# main.net
KiCad netlist of a schematic drawn in EAGLE
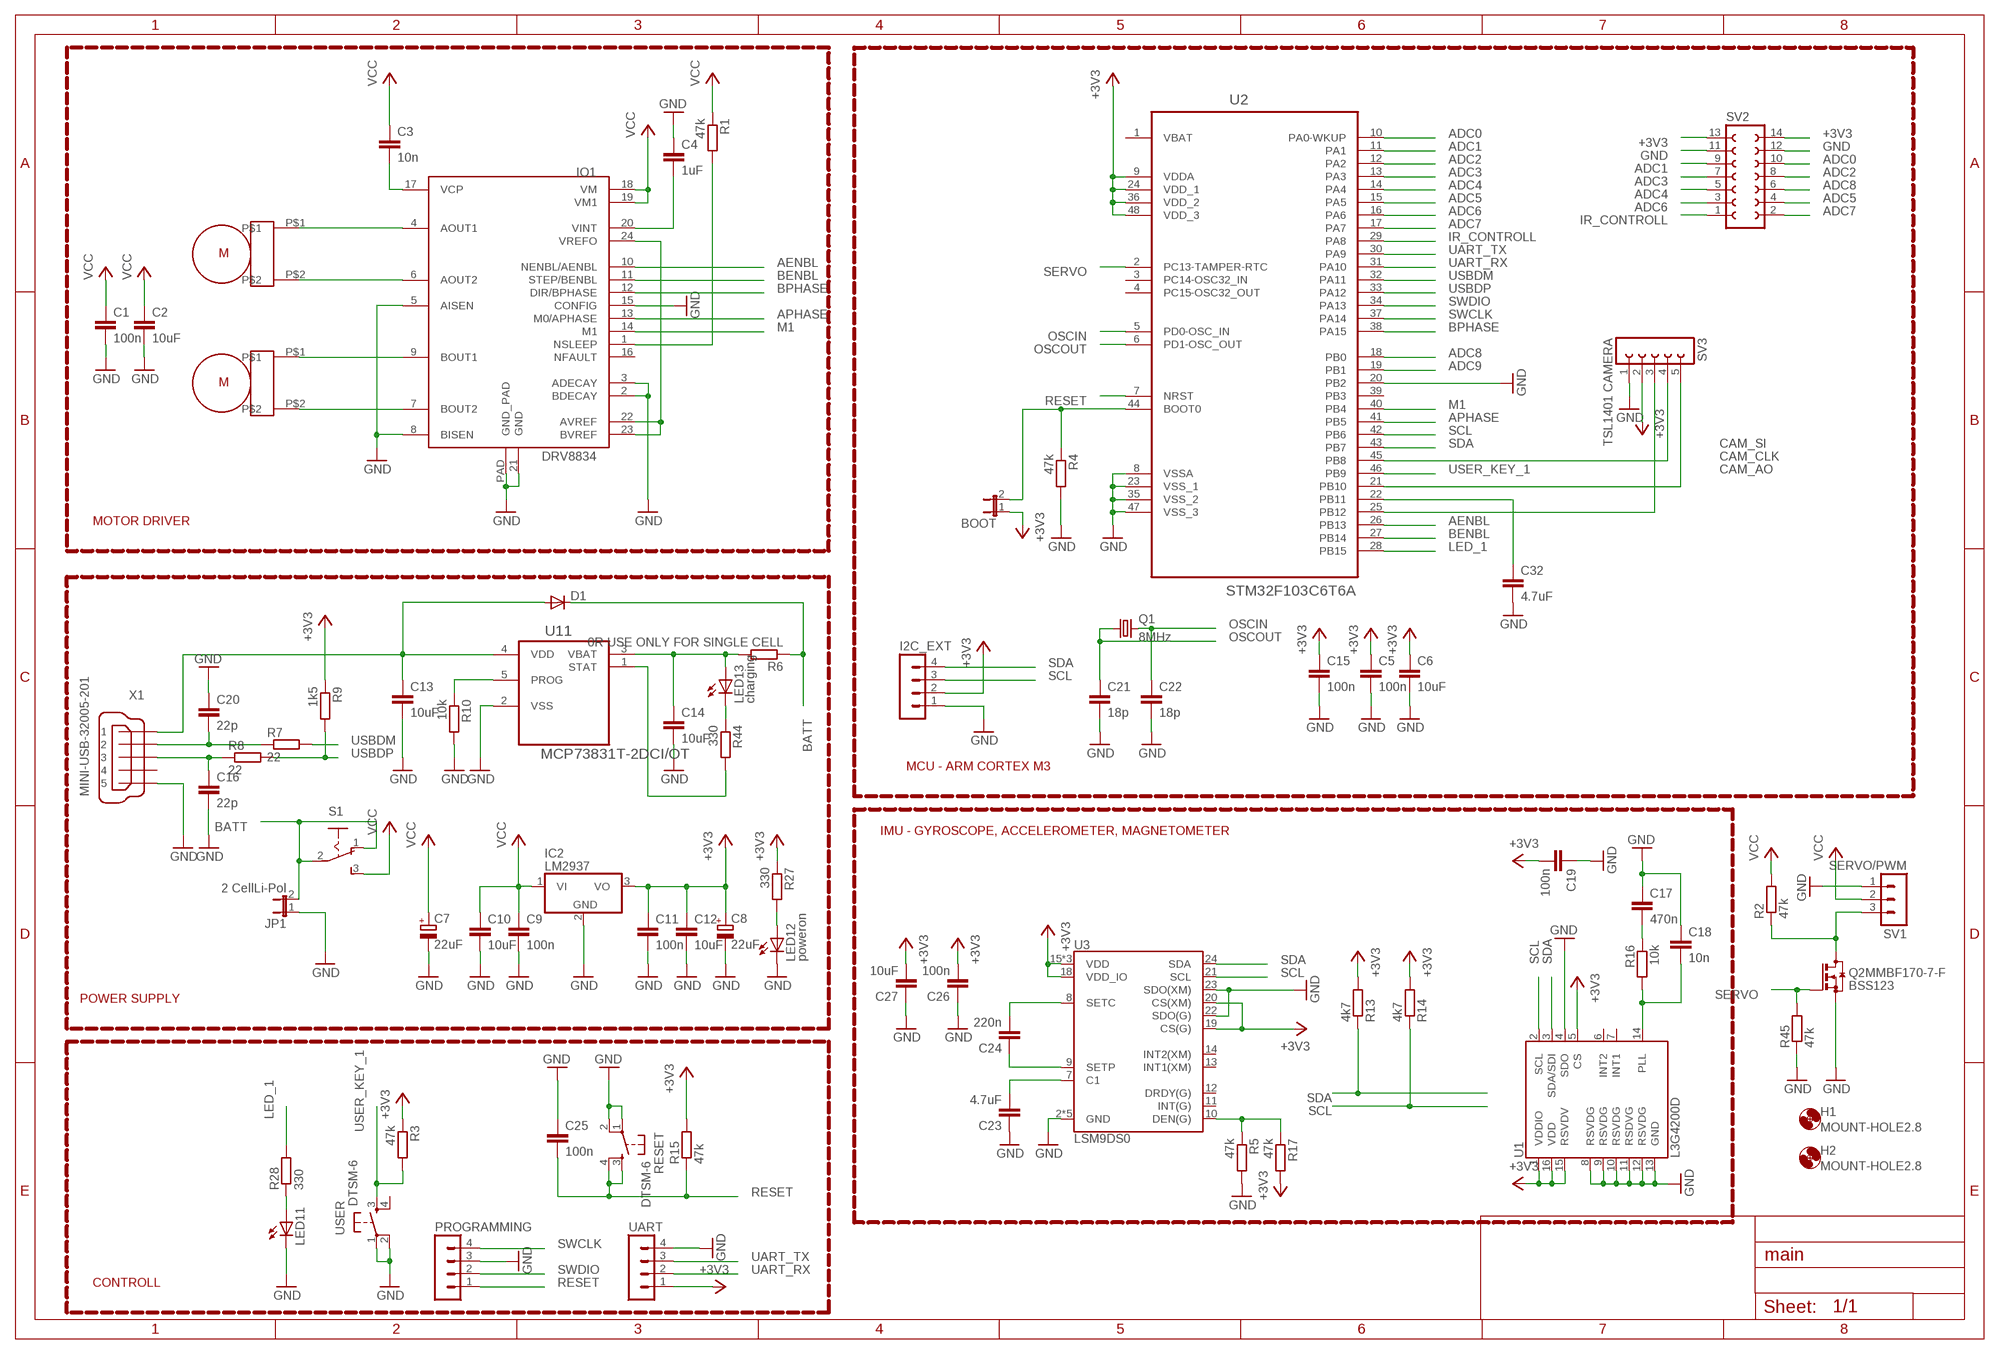
[diagram p0: schematic, sheet 1]

(export (version "E")
  (design (tool "Eeschema 10.0.6"))
  (components
    (comp (ref "BOOT")
      (value "JP1E")
      (footprint "eagle-import:JP1")
      (libsource (lib "eagle-import") (part "JP1E"))
    )
    (comp (ref "C1")
      (value "100n")
      (footprint "eagle-import:C1206")
      (libsource (lib "eagle-import") (part "C-EUC1206"))
    )
    (comp (ref "C2")
      (value "10uF")
      (footprint "eagle-import:C1206")
      (libsource (lib "eagle-import") (part "C-EUC1206"))
    )
    (comp (ref "C3")
      (value "10n")
      (footprint "eagle-import:C1206")
      (libsource (lib "eagle-import") (part "C-EUC1206"))
    )
    (comp (ref "C4")
      (value "1uF")
      (footprint "eagle-import:C1206")
      (libsource (lib "eagle-import") (part "C-EUC1206"))
    )
    (comp (ref "C5")
      (value "100n")
      (footprint "eagle-import:C0805")
      (libsource (lib "eagle-import") (part "C-EUC0805"))
    )
    (comp (ref "C6")
      (value "10uF")
      (footprint "eagle-import:C0805")
      (libsource (lib "eagle-import") (part "C-EUC0805"))
    )
    (comp (ref "C7")
      (value "22uF")
      (footprint "eagle-import:153CLV-0505")
      (libsource (lib "eagle-import") (part "CPOL-EU153CLV-0505"))
    )
    (comp (ref "C8")
      (value "22uF")
      (footprint "eagle-import:153CLV-0505")
      (libsource (lib "eagle-import") (part "CPOL-EU153CLV-0505"))
    )
    (comp (ref "C9")
      (value "100n")
      (footprint "eagle-import:C0805")
      (libsource (lib "eagle-import") (part "C-EUC0805"))
    )
    (comp (ref "C10")
      (value "10uF")
      (footprint "eagle-import:C0805")
      (libsource (lib "eagle-import") (part "C-EUC0805"))
    )
    (comp (ref "C11")
      (value "100n")
      (footprint "eagle-import:C0805")
      (libsource (lib "eagle-import") (part "C-EUC0805"))
    )
    (comp (ref "C12")
      (value "10uF")
      (footprint "eagle-import:C0805")
      (libsource (lib "eagle-import") (part "C-EUC0805"))
    )
    (comp (ref "C13")
      (value "10uF")
      (footprint "eagle-import:C0805")
      (libsource (lib "eagle-import") (part "C-EUC0805"))
    )
    (comp (ref "C14")
      (value "10uF")
      (footprint "eagle-import:C0805")
      (libsource (lib "eagle-import") (part "C-EUC0805"))
    )
    (comp (ref "C15")
      (value "100n")
      (footprint "eagle-import:C0805")
      (libsource (lib "eagle-import") (part "C-EUC0805"))
    )
    (comp (ref "C16")
      (value "22p")
      (footprint "eagle-import:C0805")
      (libsource (lib "eagle-import") (part "C-EUC0805"))
    )
    (comp (ref "C17")
      (value "470n")
      (footprint "eagle-import:C0805")
      (libsource (lib "eagle-import") (part "C-EUC0805"))
    )
    (comp (ref "C18")
      (value "10n")
      (footprint "eagle-import:C0805")
      (libsource (lib "eagle-import") (part "C-EUC0805"))
    )
    (comp (ref "C19")
      (value "100n")
      (footprint "eagle-import:C0805")
      (libsource (lib "eagle-import") (part "C-EUC0805"))
    )
    (comp (ref "C20")
      (value "22p")
      (footprint "eagle-import:C0805")
      (libsource (lib "eagle-import") (part "C-EUC0805"))
    )
    (comp (ref "C21")
      (value "18p")
      (footprint "eagle-import:C0805")
      (libsource (lib "eagle-import") (part "C-EUC0805"))
    )
    (comp (ref "C22")
      (value "18p")
      (footprint "eagle-import:C0805")
      (libsource (lib "eagle-import") (part "C-EUC0805"))
    )
    (comp (ref "C23")
      (value "4.7uF")
      (footprint "eagle-import:C0805")
      (libsource (lib "eagle-import") (part "C-EUC0805"))
    )
    (comp (ref "C24")
      (value "220n")
      (footprint "eagle-import:C0805")
      (libsource (lib "eagle-import") (part "C-EUC0805"))
    )
    (comp (ref "C25")
      (value "100n")
      (footprint "eagle-import:C0805")
      (libsource (lib "eagle-import") (part "C-EUC0805"))
    )
    (comp (ref "C26")
      (value "100n")
      (footprint "eagle-import:C0805")
      (libsource (lib "eagle-import") (part "C-EUC0805"))
    )
    (comp (ref "C27")
      (value "10uF")
      (footprint "eagle-import:C0805")
      (libsource (lib "eagle-import") (part "C-EUC0805"))
    )
    (comp (ref "C32")
      (value "4.7uF")
      (footprint "eagle-import:C0805")
      (libsource (lib "eagle-import") (part "C-EUC0805"))
    )
    (comp (ref "D1")
      (value "DIODE-SMB")
      (footprint "eagle-import:SMB")
      (libsource (lib "eagle-import") (part "DIODE-SMB"))
    )
    (comp (ref "H1")
      (value "MOUNT-HOLE2.8")
      (footprint "eagle-import:2,8")
      (libsource (lib "eagle-import") (part "MOUNT-HOLE2.8"))
    )
    (comp (ref "H2")
      (value "MOUNT-HOLE2.8")
      (footprint "eagle-import:2,8")
      (libsource (lib "eagle-import") (part "MOUNT-HOLE2.8"))
    )
    (comp (ref "I2C_EXT")
      (value "MA04-1")
      (footprint "eagle-import:MA04-1")
      (libsource (lib "eagle-import") (part "MA04-1"))
    )
    (comp (ref "IC2")
      (value "LM2937")
      (footprint "eagle-import:TO263-3")
      (libsource (lib "eagle-import") (part "LM2937"))
    )
    (comp (ref "IO1")
      (value "DRV8834")
      (footprint "eagle-import:DRV8834_PCK")
      (libsource (lib "eagle-import") (part "DRV8834"))
    )
    (comp (ref "JP1")
      (value "2 CellLi-Pol")
      (footprint "eagle-import:JP1")
      (libsource (lib "eagle-import") (part "JP1E"))
    )
    (comp (ref "LED11")
      (value "LEDCHIPLED_1206")
      (footprint "eagle-import:CHIPLED_1206")
      (libsource (lib "eagle-import") (part "LEDCHIPLED_1206"))
    )
    (comp (ref "LED12")
      (value "poweron")
      (footprint "eagle-import:CHIPLED_1206")
      (libsource (lib "eagle-import") (part "LEDCHIPLED_1206"))
    )
    (comp (ref "LED13")
      (value "charging")
      (footprint "eagle-import:CHIPLED_1206")
      (libsource (lib "eagle-import") (part "LEDCHIPLED_1206"))
    )
    (comp (ref "PROGRAMMING")
      (value "MA04-1")
      (footprint "eagle-import:MA04-1")
      (libsource (lib "eagle-import") (part "MA04-1"))
    )
    (comp (ref "Q1")
      (value "8MHz")
      (footprint "eagle-import:CTS406")
      (libsource (lib "eagle-import") (part "CRYSTALCTS406"))
    )
    (comp (ref "Q2MMBF170-7-F")
      (value "BSS123")
      (footprint "eagle-import:SOT23")
      (libsource (lib "eagle-import") (part "BSS123"))
    )
    (comp (ref "R1")
      (value "47k")
      (footprint "eagle-import:M1206")
      (libsource (lib "eagle-import") (part "R-EU_M1206"))
    )
    (comp (ref "R2")
      (value "47k")
      (footprint "eagle-import:M0805")
      (libsource (lib "eagle-import") (part "R-EU_M0805"))
    )
    (comp (ref "R3")
      (value "47k")
      (footprint "eagle-import:M0805")
      (libsource (lib "eagle-import") (part "R-EU_M0805"))
    )
    (comp (ref "R4")
      (value "47k")
      (footprint "eagle-import:M0805")
      (libsource (lib "eagle-import") (part "R-EU_M0805"))
    )
    (comp (ref "R5")
      (value "47k")
      (footprint "eagle-import:M0805")
      (libsource (lib "eagle-import") (part "R-EU_M0805"))
    )
    (comp (ref "R6")
      (value "0R USE ONLY FOR SINGLE CELL")
      (footprint "eagle-import:M1206")
      (libsource (lib "eagle-import") (part "R-EU_M1206"))
    )
    (comp (ref "R7")
      (value "22")
      (footprint "eagle-import:M0805")
      (libsource (lib "eagle-import") (part "R-EU_M0805"))
    )
    (comp (ref "R8")
      (value "22")
      (footprint "eagle-import:M0805")
      (libsource (lib "eagle-import") (part "R-EU_M0805"))
    )
    (comp (ref "R9")
      (value "1k5")
      (footprint "eagle-import:M0805")
      (libsource (lib "eagle-import") (part "R-EU_M0805"))
    )
    (comp (ref "R10")
      (value "10k")
      (footprint "eagle-import:M0805")
      (libsource (lib "eagle-import") (part "R-EU_M0805"))
    )
    (comp (ref "R13")
      (value "4k7")
      (footprint "eagle-import:M0805")
      (libsource (lib "eagle-import") (part "R-EU_M0805"))
    )
    (comp (ref "R14")
      (value "4k7")
      (footprint "eagle-import:M0805")
      (libsource (lib "eagle-import") (part "R-EU_M0805"))
    )
    (comp (ref "R15")
      (value "47k")
      (footprint "eagle-import:M0805")
      (libsource (lib "eagle-import") (part "R-EU_M0805"))
    )
    (comp (ref "R16")
      (value "10k")
      (footprint "eagle-import:M0805")
      (libsource (lib "eagle-import") (part "R-EU_M0805"))
    )
    (comp (ref "R17")
      (value "47k")
      (footprint "eagle-import:M0805")
      (libsource (lib "eagle-import") (part "R-EU_M0805"))
    )
    (comp (ref "R27")
      (value "330")
      (footprint "eagle-import:M0805")
      (libsource (lib "eagle-import") (part "R-EU_M0805"))
    )
    (comp (ref "R28")
      (value "330")
      (footprint "eagle-import:M0805")
      (libsource (lib "eagle-import") (part "R-EU_M0805"))
    )
    (comp (ref "R44")
      (value "330")
      (footprint "eagle-import:M0805")
      (libsource (lib "eagle-import") (part "R-EU_M0805"))
    )
    (comp (ref "R45")
      (value "47k")
      (footprint "eagle-import:M0805")
      (libsource (lib "eagle-import") (part "R-EU_M0805"))
    )
    (comp (ref "RESET")
      (value "DTSM-6")
      (footprint "eagle-import:DTSM-6")
      (libsource (lib "eagle-import") (part "DTSM-6"))
    )
    (comp (ref "S1")
      (value "255SB")
      (footprint "eagle-import:255SB")
      (libsource (lib "eagle-import") (part "255SB"))
    )
    (comp (ref "SV1")
      (value "SERVO/PWM")
      (footprint "eagle-import:MA03-1")
      (libsource (lib "eagle-import") (part "MA03-1"))
    )
    (comp (ref "SV2")
      (value "FE07-2")
      (footprint "eagle-import:FE07-2")
      (libsource (lib "eagle-import") (part "FE07-2"))
    )
    (comp (ref "SV3")
      (value "TSL1401 CAMERA")
      (footprint "eagle-import:FE05-1")
      (libsource (lib "eagle-import") (part "FE05-1"))
    )
    (comp (ref "U$1")
      (value "MICRO_METAL_GEAR_MOTOR")
      (footprint "eagle-import:MICRO_METAL_GEAR_MOTOR")
      (libsource (lib "eagle-import") (part "MICRO_METAL_GEAR_MOTOR"))
    )
    (comp (ref "U$2")
      (value "MICRO_METAL_GEAR_MOTOR")
      (footprint "eagle-import:MICRO_METAL_GEAR_MOTOR")
      (libsource (lib "eagle-import") (part "MICRO_METAL_GEAR_MOTOR"))
    )
    (comp (ref "U1")
      (value "L3G4200D")
      (footprint "eagle-import:LGA16-4X4")
      (libsource (lib "eagle-import") (part "L3G4200D"))
    )
    (comp (ref "U2")
      (value "STM32F103C6T6A")
      (footprint "eagle-import:QFP50P900X900X160-48N")
      (libsource (lib "eagle-import") (part "STM32F103C6T6A"))
    )
    (comp (ref "U3")
      (value "LSM9DS0")
      (footprint "eagle-import:LGA-24")
      (libsource (lib "eagle-import") (part "LSM9DS0"))
    )
    (comp (ref "U11")
      (value "MCP73831T-2DCI/OT")
      (footprint "eagle-import:SOT95P270X145-5N")
      (libsource (lib "eagle-import") (part "MCP73831T-2DCI/OT"))
    )
    (comp (ref "UART")
      (value "MA04-1")
      (footprint "eagle-import:MA04-1")
      (libsource (lib "eagle-import") (part "MA04-1"))
    )
    (comp (ref "USER")
      (value "DTSM-6")
      (footprint "eagle-import:DTSM-6")
      (libsource (lib "eagle-import") (part "DTSM-6"))
    )
    (comp (ref "X1")
      (value "MINI-USB-32005-201")
      (footprint "eagle-import:32005-201")
      (libsource (lib "eagle-import") (part "MINI-USB-32005-201"))
    )
  )
  (nets
    (net (code "1") (name "+3V3") (class "Default")
      (node (ref "BOOT") (pin "1") (pinfunction "1_1") (pintype "passive"))
      (node (ref "C11") (pin "1") (pinfunction "1_1") (pintype "passive"))
      (node (ref "C12") (pin "1") (pinfunction "1_1") (pintype "passive"))
      (node (ref "C15") (pin "1") (pinfunction "1_1") (pintype "passive"))
      (node (ref "C19") (pin "2") (pinfunction "2_2") (pintype "passive"))
      (node (ref "C26") (pin "2") (pinfunction "2_2") (pintype "passive"))
      (node (ref "C27") (pin "2") (pinfunction "2_2") (pintype "passive"))
      (node (ref "C5") (pin "1") (pinfunction "1_1") (pintype "passive"))
      (node (ref "C6") (pin "1") (pinfunction "1_1") (pintype "passive"))
      (node (ref "C8") (pin "+") (pinfunction "+_+") (pintype "passive"))
      (node (ref "I2C_EXT") (pin "2") (pinfunction "2_2") (pintype "passive"))
      (node (ref "IC2") (pin "3") (pinfunction "VO_3") (pintype "passive"))
      (node (ref "R13") (pin "2") (pinfunction "2_2") (pintype "passive"))
      (node (ref "R14") (pin "2") (pinfunction "2_2") (pintype "passive"))
      (node (ref "R15") (pin "2") (pinfunction "2_2") (pintype "passive"))
      (node (ref "R17") (pin "2") (pinfunction "2_2") (pintype "passive"))
      (node (ref "R27") (pin "1") (pinfunction "1_1") (pintype "passive"))
      (node (ref "R3") (pin "1") (pinfunction "1_1") (pintype "passive"))
      (node (ref "R9") (pin "1") (pinfunction "1_1") (pintype "passive"))
      (node (ref "SV2") (pin "13") (pinfunction "13_13") (pintype "passive"))
      (node (ref "SV2") (pin "14") (pinfunction "14_14") (pintype "passive"))
      (node (ref "SV3") (pin "2") (pinfunction "2_2") (pintype "passive"))
      (node (ref "U1") (pin "1") (pinfunction "VDDIO_1") (pintype "bidirectional"))
      (node (ref "U1") (pin "15") (pinfunction "RSVDV_15") (pintype "bidirectional"))
      (node (ref "U1") (pin "16") (pinfunction "VDD_16") (pintype "bidirectional"))
      (node (ref "U1") (pin "5") (pinfunction "CS_5") (pintype "bidirectional"))
      (node (ref "U2") (pin "24") (pinfunction "VDD_1_24") (pintype "power_in"))
      (node (ref "U2") (pin "36") (pinfunction "VDD_2_36") (pintype "power_in"))
      (node (ref "U2") (pin "48") (pinfunction "VDD_3_48") (pintype "power_in"))
      (node (ref "U2") (pin "9") (pinfunction "VDDA_9") (pintype "power_in"))
      (node (ref "U3") (pin "15") (pinfunction "VDD_15") (pintype "bidirectional"))
      (node (ref "U3") (pin "16") (pinfunction "VDD_16") (pintype "bidirectional"))
      (node (ref "U3") (pin "17") (pinfunction "VDD_17") (pintype "bidirectional"))
      (node (ref "U3") (pin "18") (pinfunction "VDD_IO_18") (pintype "bidirectional"))
      (node (ref "U3") (pin "19") (pinfunction "CS(G)_19") (pintype "bidirectional"))
      (node (ref "U3") (pin "20") (pinfunction "CS(XM)_20") (pintype "bidirectional"))
      (node (ref "UART") (pin "1") (pinfunction "1_1") (pintype "passive"))
    )
    (net (code "2") (name "/ADC0") (class "Default")
      (node (ref "SV2") (pin "10") (pinfunction "10_10") (pintype "passive"))
      (node (ref "U2") (pin "10") (pinfunction "PA0-WKUP_10") (pintype "bidirectional"))
    )
    (net (code "3") (name "/ADC1") (class "Default")
      (node (ref "SV2") (pin "9") (pinfunction "9_9") (pintype "passive"))
      (node (ref "U2") (pin "11") (pinfunction "PA1_11") (pintype "bidirectional"))
    )
    (net (code "4") (name "/ADC2") (class "Default")
      (node (ref "SV2") (pin "8") (pinfunction "8_8") (pintype "passive"))
      (node (ref "U2") (pin "12") (pinfunction "PA2_12") (pintype "bidirectional"))
    )
    (net (code "5") (name "/ADC3") (class "Default")
      (node (ref "SV2") (pin "7") (pinfunction "7_7") (pintype "passive"))
      (node (ref "U2") (pin "13") (pinfunction "PA3_13") (pintype "bidirectional"))
    )
    (net (code "6") (name "/ADC4") (class "Default")
      (node (ref "SV2") (pin "5") (pinfunction "5_5") (pintype "passive"))
      (node (ref "U2") (pin "14") (pinfunction "PA4_14") (pintype "bidirectional"))
    )
    (net (code "7") (name "/ADC5") (class "Default")
      (node (ref "SV2") (pin "4") (pinfunction "4_4") (pintype "passive"))
      (node (ref "U2") (pin "15") (pinfunction "PA5_15") (pintype "bidirectional"))
    )
    (net (code "8") (name "/ADC6") (class "Default")
      (node (ref "SV2") (pin "3") (pinfunction "3_3") (pintype "passive"))
      (node (ref "U2") (pin "16") (pinfunction "PA6_16") (pintype "bidirectional"))
    )
    (net (code "9") (name "/ADC7") (class "Default")
      (node (ref "SV2") (pin "2") (pinfunction "2_2") (pintype "passive"))
      (node (ref "U2") (pin "17") (pinfunction "PA7_17") (pintype "bidirectional"))
    )
    (net (code "10") (name "/ADC8") (class "Default")
      (node (ref "SV2") (pin "6") (pinfunction "6_6") (pintype "passive"))
      (node (ref "U2") (pin "18") (pinfunction "PB0_18") (pintype "bidirectional"))
    )
    (net (code "11") (name "/ADC9") (class "Default")
      (node (ref "U2") (pin "19") (pinfunction "PB1_19") (pintype "bidirectional"))
    )
    (net (code "12") (name "/AENBL") (class "Default")
      (node (ref "IO1") (pin "10") (pinfunction "NENBL/AENBL_10") (pintype "bidirectional"))
      (node (ref "U2") (pin "26") (pinfunction "PB13_26") (pintype "bidirectional"))
    )
    (net (code "13") (name "/APHASE") (class "Default")
      (node (ref "IO1") (pin "13") (pinfunction "M0/APHASE_13") (pintype "bidirectional"))
      (node (ref "U2") (pin "41") (pinfunction "PB5_41") (pintype "bidirectional"))
    )
    (net (code "14") (name "/BATT") (class "Default")
      (node (ref "D1") (pin "C") (pinfunction "C_C") (pintype "passive"))
      (node (ref "JP1") (pin "2") (pinfunction "2_2") (pintype "passive"))
      (node (ref "R6") (pin "1") (pinfunction "1_1") (pintype "passive"))
      (node (ref "S1") (pin "1") (pinfunction "O_1") (pintype "passive"))
      (node (ref "S1") (pin "2") (pinfunction "P_2") (pintype "passive"))
    )
    (net (code "15") (name "/BENBL") (class "Default")
      (node (ref "IO1") (pin "11") (pinfunction "STEP/BENBL_11") (pintype "bidirectional"))
      (node (ref "U2") (pin "27") (pinfunction "PB14_27") (pintype "bidirectional"))
    )
    (net (code "16") (name "/BPHASE") (class "Default")
      (node (ref "IO1") (pin "12") (pinfunction "DIR/BPHASE_12") (pintype "bidirectional"))
      (node (ref "U2") (pin "38") (pinfunction "PA15_38") (pintype "bidirectional"))
    )
    (net (code "17") (name "/CAM_AO") (class "Default")
      (node (ref "SV3") (pin "3") (pinfunction "3_3") (pintype "passive"))
      (node (ref "U2") (pin "25") (pinfunction "PB12_25") (pintype "bidirectional"))
    )
    (net (code "18") (name "/CAM_CLK") (class "Default")
      (node (ref "SV3") (pin "4") (pinfunction "4_4") (pintype "passive"))
      (node (ref "U2") (pin "45") (pinfunction "PB8_45") (pintype "bidirectional"))
    )
    (net (code "19") (name "/CAM_SI") (class "Default")
      (node (ref "SV3") (pin "5") (pinfunction "5_5") (pintype "passive"))
      (node (ref "U2") (pin "21") (pinfunction "PB10_21") (pintype "bidirectional"))
    )
    (net (code "20") (name "/IR_CONTROLL") (class "Default")
      (node (ref "SV2") (pin "1") (pinfunction "1_1") (pintype "passive"))
      (node (ref "U2") (pin "29") (pinfunction "PA8_29") (pintype "bidirectional"))
    )
    (net (code "21") (name "/LED_1") (class "Default")
      (node (ref "R28") (pin "2") (pinfunction "2_2") (pintype "passive"))
      (node (ref "U2") (pin "28") (pinfunction "PB15_28") (pintype "bidirectional"))
    )
    (net (code "22") (name "/M1") (class "Default")
      (node (ref "IO1") (pin "14") (pinfunction "M1_14") (pintype "bidirectional"))
      (node (ref "U2") (pin "40") (pinfunction "PB4_40") (pintype "bidirectional"))
    )
    (net (code "23") (name "/OSCIN") (class "Default")
      (node (ref "C22") (pin "1") (pinfunction "1_1") (pintype "passive"))
      (node (ref "Q1") (pin "3") (pinfunction "2_3") (pintype "passive"))
      (node (ref "U2") (pin "5") (pinfunction "PD0-OSC_IN_5") (pintype "bidirectional"))
    )
    (net (code "24") (name "/OSCOUT") (class "Default")
      (node (ref "C21") (pin "1") (pinfunction "1_1") (pintype "passive"))
      (node (ref "Q1") (pin "1") (pinfunction "1_1") (pintype "passive"))
      (node (ref "U2") (pin "6") (pinfunction "PD1-OSC_OUT_6") (pintype "bidirectional"))
    )
    (net (code "25") (name "/RESET") (class "Default")
      (node (ref "C25") (pin "2") (pinfunction "2_2") (pintype "passive"))
      (node (ref "PROGRAMMING") (pin "1") (pinfunction "1_1") (pintype "passive"))
      (node (ref "R15") (pin "1") (pinfunction "1_1") (pintype "passive"))
      (node (ref "RESET") (pin "3") (pinfunction "3_3") (pintype "passive"))
      (node (ref "RESET") (pin "4") (pinfunction "4_4") (pintype "passive"))
      (node (ref "U2") (pin "7") (pinfunction "NRST_7") (pintype "bidirectional"))
    )
    (net (code "26") (name "/SCL") (class "Default")
      (node (ref "I2C_EXT") (pin "3") (pinfunction "3_3") (pintype "passive"))
      (node (ref "R14") (pin "1") (pinfunction "1_1") (pintype "passive"))
      (node (ref "U1") (pin "2") (pinfunction "SCL_2") (pintype "bidirectional"))
      (node (ref "U2") (pin "42") (pinfunction "PB6_42") (pintype "bidirectional"))
      (node (ref "U3") (pin "21") (pinfunction "SCL_21") (pintype "bidirectional"))
    )
    (net (code "27") (name "/SDA") (class "Default")
      (node (ref "I2C_EXT") (pin "4") (pinfunction "4_4") (pintype "passive"))
      (node (ref "R13") (pin "1") (pinfunction "1_1") (pintype "passive"))
      (node (ref "U1") (pin "3") (pinfunction "SDA/SDI_3") (pintype "bidirectional"))
      (node (ref "U2") (pin "43") (pinfunction "PB7_43") (pintype "bidirectional"))
      (node (ref "U3") (pin "24") (pinfunction "SDA_24") (pintype "bidirectional"))
    )
    (net (code "28") (name "/SERVO") (class "Default")
      (node (ref "Q2MMBF170-7-F") (pin "1") (pinfunction "G_1") (pintype "passive"))
      (node (ref "R45") (pin "2") (pinfunction "2_2") (pintype "passive"))
      (node (ref "U2") (pin "2") (pinfunction "PC13-TAMPER-RTC_2") (pintype "bidirectional"))
    )
    (net (code "29") (name "/SWCLK") (class "Default")
      (node (ref "PROGRAMMING") (pin "4") (pinfunction "4_4") (pintype "passive"))
      (node (ref "U2") (pin "37") (pinfunction "PA14_37") (pintype "bidirectional"))
    )
    (net (code "30") (name "/SWDIO") (class "Default")
      (node (ref "PROGRAMMING") (pin "2") (pinfunction "2_2") (pintype "passive"))
      (node (ref "U2") (pin "34") (pinfunction "PA13_34") (pintype "bidirectional"))
    )
    (net (code "31") (name "/UART_RX") (class "Default")
      (node (ref "U2") (pin "31") (pinfunction "PA10_31") (pintype "bidirectional"))
      (node (ref "UART") (pin "2") (pinfunction "2_2") (pintype "passive"))
    )
    (net (code "32") (name "/UART_TX") (class "Default")
      (node (ref "U2") (pin "30") (pinfunction "PA9_30") (pintype "bidirectional"))
      (node (ref "UART") (pin "3") (pinfunction "3_3") (pintype "passive"))
    )
    (net (code "33") (name "/USBDM") (class "Default")
      (node (ref "R7") (pin "2") (pinfunction "2_2") (pintype "passive"))
      (node (ref "U2") (pin "32") (pinfunction "PA11_32") (pintype "bidirectional"))
    )
    (net (code "34") (name "/USBDP") (class "Default")
      (node (ref "R8") (pin "2") (pinfunction "2_2") (pintype "passive"))
      (node (ref "R9") (pin "2") (pinfunction "2_2") (pintype "passive"))
      (node (ref "U2") (pin "33") (pinfunction "PA12_33") (pintype "bidirectional"))
    )
    (net (code "35") (name "/USER_KEY_1") (class "Default")
      (node (ref "R3") (pin "2") (pinfunction "2_2") (pintype "passive"))
      (node (ref "U2") (pin "46") (pinfunction "PB9_46") (pintype "bidirectional"))
      (node (ref "USER") (pin "3") (pinfunction "3_3") (pintype "passive"))
    )
    (net (code "36") (name "/VBAT") (class "Default")
      (node (ref "U2") (pin "1") (pinfunction "VBAT_1") (pintype "power_in"))
    )
    (net (code "37") (name "GND") (class "Default")
      (node (ref "C1") (pin "2") (pinfunction "2_2") (pintype "passive"))
      (node (ref "C10") (pin "2") (pinfunction "2_2") (pintype "passive"))
      (node (ref "C11") (pin "2") (pinfunction "2_2") (pintype "passive"))
      (node (ref "C12") (pin "2") (pinfunction "2_2") (pintype "passive"))
      (node (ref "C13") (pin "2") (pinfunction "2_2") (pintype "passive"))
      (node (ref "C14") (pin "2") (pinfunction "2_2") (pintype "passive"))
      (node (ref "C15") (pin "2") (pinfunction "2_2") (pintype "passive"))
      (node (ref "C16") (pin "2") (pinfunction "2_2") (pintype "passive"))
      (node (ref "C17") (pin "1") (pinfunction "1_1") (pintype "passive"))
      (node (ref "C18") (pin "1") (pinfunction "1_1") (pintype "passive"))
      (node (ref "C19") (pin "1") (pinfunction "1_1") (pintype "passive"))
      (node (ref "C2") (pin "2") (pinfunction "2_2") (pintype "passive"))
      (node (ref "C20") (pin "1") (pinfunction "1_1") (pintype "passive"))
      (node (ref "C21") (pin "2") (pinfunction "2_2") (pintype "passive"))
      (node (ref "C22") (pin "2") (pinfunction "2_2") (pintype "passive"))
      (node (ref "C23") (pin "1") (pinfunction "1_1") (pintype "passive"))
      (node (ref "C25") (pin "1") (pinfunction "1_1") (pintype "passive"))
      (node (ref "C26") (pin "1") (pinfunction "1_1") (pintype "passive"))
      (node (ref "C27") (pin "1") (pinfunction "1_1") (pintype "passive"))
      (node (ref "C32") (pin "2") (pinfunction "2_2") (pintype "passive"))
      (node (ref "C4") (pin "1") (pinfunction "1_1") (pintype "passive"))
      (node (ref "C5") (pin "2") (pinfunction "2_2") (pintype "passive"))
      (node (ref "C6") (pin "2") (pinfunction "2_2") (pintype "passive"))
      (node (ref "C7") (pin "-") (pinfunction "-_-") (pintype "passive"))
      (node (ref "C8") (pin "-") (pinfunction "-_-") (pintype "passive"))
      (node (ref "C9") (pin "2") (pinfunction "2_2") (pintype "passive"))
      (node (ref "I2C_EXT") (pin "1") (pinfunction "1_1") (pintype "passive"))
      (node (ref "IC2") (pin "2") (pinfunction "GND_2") (pintype "passive"))
      (node (ref "IO1") (pin "15") (pinfunction "CONFIG_15") (pintype "bidirectional"))
      (node (ref "IO1") (pin "2") (pinfunction "BDECAY_2") (pintype "bidirectional"))
      (node (ref "IO1") (pin "21") (pinfunction "GND_21") (pintype "bidirectional"))
      (node (ref "IO1") (pin "3") (pinfunction "ADECAY_3") (pintype "bidirectional"))
      (node (ref "IO1") (pin "5") (pinfunction "AISEN_5") (pintype "bidirectional"))
      (node (ref "IO1") (pin "8") (pinfunction "BISEN_8") (pintype "bidirectional"))
      (node (ref "IO1") (pin "PAD") (pinfunction "GND_PAD_PAD") (pintype "bidirectional"))
      (node (ref "JP1") (pin "1") (pinfunction "1_1") (pintype "passive"))
      (node (ref "LED11") (pin "C") (pinfunction "C_C") (pintype "passive"))
      (node (ref "LED12") (pin "C") (pinfunction "C_C") (pintype "passive"))
      (node (ref "PROGRAMMING") (pin "3") (pinfunction "3_3") (pintype "passive"))
      (node (ref "Q2MMBF170-7-F") (pin "2") (pinfunction "S_2") (pintype "passive"))
      (node (ref "R10") (pin "2") (pinfunction "2_2") (pintype "passive"))
      (node (ref "R4") (pin "2") (pinfunction "2_2") (pintype "passive"))
      (node (ref "R45") (pin "1") (pinfunction "1_1") (pintype "passive"))
      (node (ref "R5") (pin "2") (pinfunction "2_2") (pintype "passive"))
      (node (ref "RESET") (pin "1") (pinfunction "1_1") (pintype "passive"))
      (node (ref "RESET") (pin "2") (pinfunction "2_2") (pintype "passive"))
      (node (ref "SV1") (pin "1") (pinfunction "1_1") (pintype "passive"))
      (node (ref "SV2") (pin "11") (pinfunction "11_11") (pintype "passive"))
      (node (ref "SV2") (pin "12") (pinfunction "12_12") (pintype "passive"))
      (node (ref "SV3") (pin "1") (pinfunction "1_1") (pintype "passive"))
      (node (ref "U1") (pin "10") (pinfunction "RSVDG_10") (pintype "bidirectional"))
      (node (ref "U1") (pin "11") (pinfunction "RSDVG_11") (pintype "bidirectional"))
      (node (ref "U1") (pin "12") (pinfunction "RSVDG_12") (pintype "bidirectional"))
      (node (ref "U1") (pin "13") (pinfunction "GND_13") (pintype "bidirectional"))
      (node (ref "U1") (pin "4") (pinfunction "SDO_4") (pintype "bidirectional"))
      (node (ref "U1") (pin "8") (pinfunction "RSVDG_8") (pintype "bidirectional"))
      (node (ref "U1") (pin "9") (pinfunction "RSVDG_9") (pintype "bidirectional"))
      (node (ref "U11") (pin "2") (pinfunction "VSS_2") (pintype "power_in"))
      (node (ref "U2") (pin "20") (pinfunction "PB2_20") (pintype "bidirectional"))
      (node (ref "U2") (pin "23") (pinfunction "VSS_1_23") (pintype "passive"))
      (node (ref "U2") (pin "35") (pinfunction "VSS_2_35") (pintype "passive"))
      (node (ref "U2") (pin "47") (pinfunction "VSS_3_47") (pintype "passive"))
      (node (ref "U2") (pin "8") (pinfunction "VSSA_8") (pintype "passive"))
      (node (ref "U3") (pin "2") (pinfunction "GND_2") (pintype "bidirectional"))
      (node (ref "U3") (pin "22") (pinfunction "SDO(G)_22") (pintype "bidirectional"))
      (node (ref "U3") (pin "23") (pinfunction "SDO(XM)_23") (pintype "bidirectional"))
      (node (ref "U3") (pin "3") (pinfunction "GND_3") (pintype "bidirectional"))
      (node (ref "U3") (pin "4") (pinfunction "GND_4") (pintype "bidirectional"))
      (node (ref "U3") (pin "5") (pinfunction "GND_5") (pintype "bidirectional"))
      (node (ref "U3") (pin "6") (pinfunction "GND_6") (pintype "bidirectional"))
      (node (ref "UART") (pin "4") (pinfunction "4_4") (pintype "passive"))
      (node (ref "USER") (pin "1") (pinfunction "1_1") (pintype "passive"))
      (node (ref "USER") (pin "2") (pinfunction "2_2") (pintype "passive"))
      (node (ref "X1") (pin "5") (pinfunction "5_5") (pintype "passive"))
    )
    (net (code "38") (name "Net-(C16-Pad1)") (class "Default")
      (node (ref "C16") (pin "1") (pinfunction "1_1") (pintype "passive"))
      (node (ref "R8") (pin "1") (pinfunction "1_1") (pintype "passive"))
      (node (ref "X1") (pin "3") (pinfunction "3_3") (pintype "passive"))
    )
    (net (code "39") (name "Net-(C17-Pad2)") (class "Default")
      (node (ref "C17") (pin "2") (pinfunction "2_2") (pintype "passive"))
      (node (ref "R16") (pin "1") (pinfunction "1_1") (pintype "passive"))
    )
    (net (code "40") (name "Net-(C20-Pad2)") (class "Default")
      (node (ref "C20") (pin "2") (pinfunction "2_2") (pintype "passive"))
      (node (ref "R7") (pin "1") (pinfunction "1_1") (pintype "passive"))
      (node (ref "X1") (pin "2") (pinfunction "2_2") (pintype "passive"))
    )
    (net (code "41") (name "Net-(IO1-AOUT1)") (class "Default")
      (node (ref "IO1") (pin "4") (pinfunction "AOUT1_4") (pintype "bidirectional"))
      (node (ref "U$1") (pin "P$1") (pinfunction "P$1_P$1") (pintype "bidirectional"))
    )
    (net (code "42") (name "Net-(IO1-AOUT2)") (class "Default")
      (node (ref "IO1") (pin "6") (pinfunction "AOUT2_6") (pintype "bidirectional"))
      (node (ref "U$1") (pin "P$2") (pinfunction "P$2_P$2") (pintype "bidirectional"))
    )
    (net (code "43") (name "Net-(IO1-AVREF)") (class "Default")
      (node (ref "IO1") (pin "22") (pinfunction "AVREF_22") (pintype "bidirectional"))
      (node (ref "IO1") (pin "23") (pinfunction "BVREF_23") (pintype "bidirectional"))
      (node (ref "IO1") (pin "24") (pinfunction "VREFO_24") (pintype "bidirectional"))
    )
    (net (code "44") (name "Net-(IO1-BOUT1)") (class "Default")
      (node (ref "IO1") (pin "9") (pinfunction "BOUT1_9") (pintype "bidirectional"))
      (node (ref "U$2") (pin "P$1") (pinfunction "P$1_P$1") (pintype "bidirectional"))
    )
    (net (code "45") (name "Net-(IO1-BOUT2)") (class "Default")
      (node (ref "IO1") (pin "7") (pinfunction "BOUT2_7") (pintype "bidirectional"))
      (node (ref "U$2") (pin "P$2") (pinfunction "P$2_P$2") (pintype "bidirectional"))
    )
    (net (code "46") (name "Net-(IO1-NSLEEP)") (class "Default")
      (node (ref "IO1") (pin "1") (pinfunction "NSLEEP_1") (pintype "bidirectional"))
      (node (ref "R1") (pin "2") (pinfunction "2_2") (pintype "passive"))
    )
    (net (code "47") (name "Net-(IO1-VCP)") (class "Default")
      (node (ref "C3") (pin "2") (pinfunction "2_2") (pintype "passive"))
      (node (ref "IO1") (pin "17") (pinfunction "VCP_17") (pintype "bidirectional"))
    )
    (net (code "48") (name "Net-(IO1-VINT)") (class "Default")
      (node (ref "C4") (pin "2") (pinfunction "2_2") (pintype "passive"))
      (node (ref "IO1") (pin "20") (pinfunction "VINT_20") (pintype "bidirectional"))
    )
    (net (code "49") (name "Net-(LED11-PadA)") (class "Default")
      (node (ref "LED11") (pin "A") (pinfunction "A_A") (pintype "passive"))
      (node (ref "R28") (pin "1") (pinfunction "1_1") (pintype "passive"))
    )
    (net (code "50") (name "Net-(LED12-PadA)") (class "Default")
      (node (ref "LED12") (pin "A") (pinfunction "A_A") (pintype "passive"))
      (node (ref "R27") (pin "2") (pinfunction "2_2") (pintype "passive"))
    )
    (net (code "51") (name "Net-(LED13-PadC)") (class "Default")
      (node (ref "LED13") (pin "C") (pinfunction "C_C") (pintype "passive"))
      (node (ref "R44") (pin "1") (pinfunction "1_1") (pintype "passive"))
    )
    (net (code "52") (name "Net-(Q2MMBF170-7-F-D)") (class "Default")
      (node (ref "Q2MMBF170-7-F") (pin "3") (pinfunction "D_3") (pintype "passive"))
      (node (ref "R2") (pin "1") (pinfunction "1_1") (pintype "passive"))
      (node (ref "SV1") (pin "3") (pinfunction "3_3") (pintype "passive"))
    )
    (net (code "53") (name "Net-(U1-PLL)") (class "Default")
      (node (ref "C18") (pin "2") (pinfunction "2_2") (pintype "passive"))
      (node (ref "R16") (pin "2") (pinfunction "2_2") (pintype "passive"))
      (node (ref "U1") (pin "14") (pinfunction "PLL_14") (pintype "bidirectional"))
    )
    (net (code "54") (name "Net-(U2-BOOT0)") (class "Default")
      (node (ref "BOOT") (pin "2") (pinfunction "2_2") (pintype "passive"))
      (node (ref "R4") (pin "1") (pinfunction "1_1") (pintype "passive"))
      (node (ref "U2") (pin "44") (pinfunction "BOOT0_44") (pintype "input"))
    )
    (net (code "55") (name "Net-(U2-PB11)") (class "Default")
      (node (ref "C32") (pin "1") (pinfunction "1_1") (pintype "passive"))
      (node (ref "U2") (pin "22") (pinfunction "PB11_22") (pintype "bidirectional"))
    )
    (net (code "56") (name "Net-(U3-C1)") (class "Default")
      (node (ref "C23") (pin "2") (pinfunction "2_2") (pintype "passive"))
      (node (ref "U3") (pin "7") (pinfunction "C1_7") (pintype "bidirectional"))
    )
    (net (code "57") (name "Net-(U3-DEN(G))") (class "Default")
      (node (ref "R17") (pin "1") (pinfunction "1_1") (pintype "passive"))
      (node (ref "R5") (pin "1") (pinfunction "1_1") (pintype "passive"))
      (node (ref "U3") (pin "10") (pinfunction "DEN(G)_10") (pintype "bidirectional"))
    )
    (net (code "58") (name "Net-(U3-SETC)") (class "Default")
      (node (ref "C24") (pin "2") (pinfunction "2_2") (pintype "passive"))
      (node (ref "U3") (pin "8") (pinfunction "SETC_8") (pintype "bidirectional"))
    )
    (net (code "59") (name "Net-(U3-SETP)") (class "Default")
      (node (ref "C24") (pin "1") (pinfunction "1_1") (pintype "passive"))
      (node (ref "U3") (pin "9") (pinfunction "SETP_9") (pintype "bidirectional"))
    )
    (net (code "60") (name "Net-(U11-PROG)") (class "Default")
      (node (ref "R10") (pin "1") (pinfunction "1_1") (pintype "passive"))
      (node (ref "U11") (pin "5") (pinfunction "PROG_5") (pintype "input"))
    )
    (net (code "61") (name "Net-(U11-STAT)") (class "Default")
      (node (ref "R44") (pin "2") (pinfunction "2_2") (pintype "passive"))
      (node (ref "U11") (pin "1") (pinfunction "STAT_1") (pintype "output"))
    )
    (net (code "62") (name "Net-(U11-VBAT)") (class "Default")
      (node (ref "C14") (pin "1") (pinfunction "1_1") (pintype "passive"))
      (node (ref "LED13") (pin "A") (pinfunction "A_A") (pintype "passive"))
      (node (ref "R6") (pin "2") (pinfunction "2_2") (pintype "passive"))
      (node (ref "U11") (pin "3") (pinfunction "VBAT_3") (pintype "power_in"))
    )
    (net (code "63") (name "Net-(U11-VDD)") (class "Default")
      (node (ref "C13") (pin "1") (pinfunction "1_1") (pintype "passive"))
      (node (ref "D1") (pin "A") (pinfunction "A_A") (pintype "passive"))
      (node (ref "U11") (pin "4") (pinfunction "VDD_4") (pintype "power_in"))
      (node (ref "X1") (pin "1") (pinfunction "1_1") (pintype "passive"))
    )
    (net (code "64") (name "VCC") (class "Default")
      (node (ref "C1") (pin "1") (pinfunction "1_1") (pintype "passive"))
      (node (ref "C10") (pin "1") (pinfunction "1_1") (pintype "passive"))
      (node (ref "C2") (pin "1") (pinfunction "1_1") (pintype "passive"))
      (node (ref "C3") (pin "1") (pinfunction "1_1") (pintype "passive"))
      (node (ref "C7") (pin "+") (pinfunction "+_+") (pintype "passive"))
      (node (ref "C9") (pin "1") (pinfunction "1_1") (pintype "passive"))
      (node (ref "IC2") (pin "1") (pinfunction "VI_1") (pintype "input"))
      (node (ref "IO1") (pin "18") (pinfunction "VM_18") (pintype "bidirectional"))
      (node (ref "IO1") (pin "19") (pinfunction "VM1_19") (pintype "bidirectional"))
      (node (ref "R1") (pin "1") (pinfunction "1_1") (pintype "passive"))
      (node (ref "R2") (pin "2") (pinfunction "2_2") (pintype "passive"))
      (node (ref "S1") (pin "3") (pinfunction "S_3") (pintype "passive"))
      (node (ref "SV1") (pin "2") (pinfunction "2_2") (pintype "passive"))
    )
    (net (code "65") (name "unconnected-(IO1-NFAULT-Pad16)") (class "Default")
      (node (ref "IO1") (pin "16") (pinfunction "NFAULT_16") (pintype "bidirectional"))
    )
    (net (code "66") (name "unconnected-(U1-INT1-Pad7)") (class "Default")
      (node (ref "U1") (pin "7") (pinfunction "INT1_7") (pintype "bidirectional"))
    )
    (net (code "67") (name "unconnected-(U1-INT2-Pad6)") (class "Default")
      (node (ref "U1") (pin "6") (pinfunction "INT2_6") (pintype "bidirectional"))
    )
    (net (code "68") (name "unconnected-(U2-PB3-Pad39)") (class "Default")
      (node (ref "U2") (pin "39") (pinfunction "PB3_39") (pintype "bidirectional"))
    )
    (net (code "69") (name "unconnected-(U2-PC14-OSC32_IN-Pad3)") (class "Default")
      (node (ref "U2") (pin "3") (pinfunction "PC14-OSC32_IN_3") (pintype "bidirectional"))
    )
    (net (code "70") (name "unconnected-(U2-PC15-OSC32_OUT-Pad4)") (class "Default")
      (node (ref "U2") (pin "4") (pinfunction "PC15-OSC32_OUT_4") (pintype "bidirectional"))
    )
    (net (code "71") (name "unconnected-(U3-DRDY(G)-Pad12)") (class "Default")
      (node (ref "U3") (pin "12") (pinfunction "DRDY(G)_12") (pintype "bidirectional"))
    )
    (net (code "72") (name "unconnected-(U3-INT(G)-Pad11)") (class "Default")
      (node (ref "U3") (pin "11") (pinfunction "INT(G)_11") (pintype "bidirectional"))
    )
    (net (code "73") (name "unconnected-(U3-INT1(XM)-Pad13)") (class "Default")
      (node (ref "U3") (pin "13") (pinfunction "INT1(XM)_13") (pintype "bidirectional"))
    )
    (net (code "74") (name "unconnected-(U3-INT2(XM)-Pad14)") (class "Default")
      (node (ref "U3") (pin "14") (pinfunction "INT2(XM)_14") (pintype "bidirectional"))
    )
    (net (code "75") (name "unconnected-(USER-Pad4)") (class "Default")
      (node (ref "USER") (pin "4") (pinfunction "4_4") (pintype "passive"))
    )
    (net (code "76") (name "unconnected-(X1-Pad4)") (class "Default")
      (node (ref "X1") (pin "4") (pinfunction "4_4") (pintype "passive"))
    )
  )
)
